# Esp32Relays.net
KiCad netlist of a schematic drawn in EAGLE
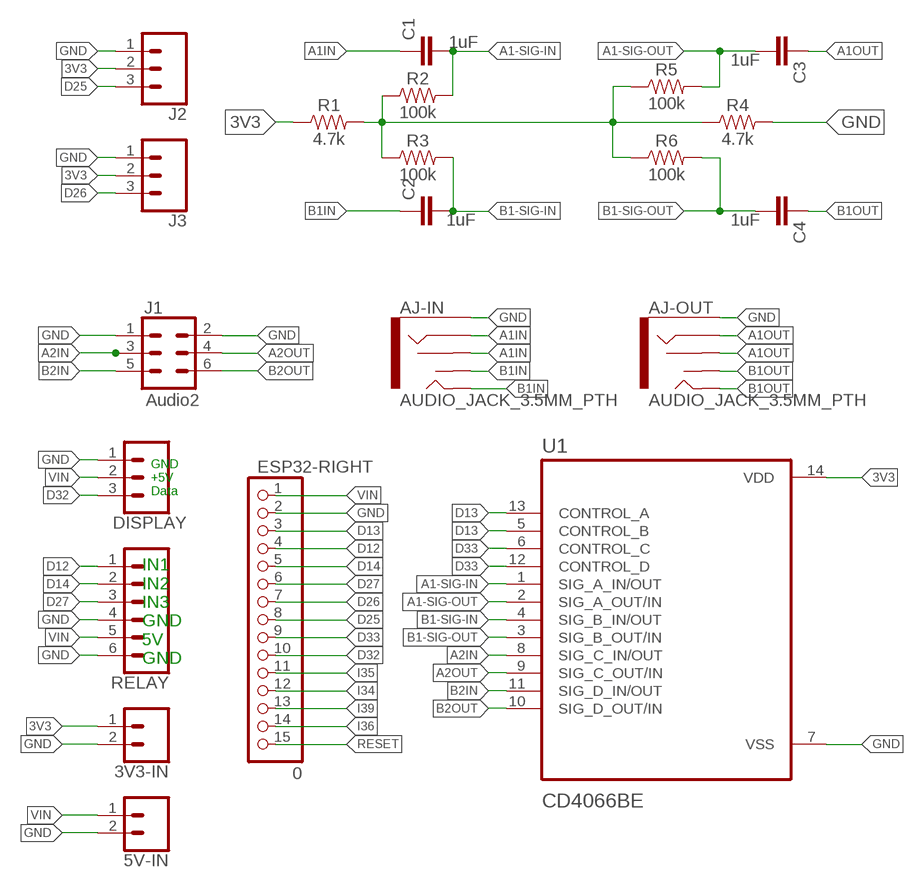
[diagram p0: schematic, sheet 1]

(export (version "E")
  (design (tool "Eeschema 10.0.6"))
  (components
    (comp (ref "3V3-IN")
      (value "CONN_02")
      (footprint "eagle-import:1X02")
      (libsource (lib "eagle-import") (part "CONN_02"))
    )
    (comp (ref "5V-IN")
      (value "CONN_02")
      (footprint "eagle-import:1X02")
      (libsource (lib "eagle-import") (part "CONN_02"))
    )
    (comp (ref "AJ-IN")
      (value "AUDIO_JACK_3.5MM_PTH")
      (footprint "eagle-import:AUDIO-JACK")
      (libsource (lib "eagle-import") (part "AUDIO_JACK_3.5MM_PTH"))
    )
    (comp (ref "AJ-OUT")
      (value "AUDIO_JACK_3.5MM_PTH")
      (footprint "eagle-import:AUDIO-JACK")
      (libsource (lib "eagle-import") (part "AUDIO_JACK_3.5MM_PTH"))
    )
    (comp (ref "C1")
      (value "1uF")
      (footprint "eagle-import:0805")
      (libsource (lib "eagle-import") (part "2.2UF-0805-25V-(+80/-20%)"))
    )
    (comp (ref "C2")
      (value "1uF")
      (footprint "eagle-import:0805")
      (libsource (lib "eagle-import") (part "2.2UF-0805-25V-(+80/-20%)"))
    )
    (comp (ref "C3")
      (value "1uF")
      (footprint "eagle-import:0805")
      (libsource (lib "eagle-import") (part "2.2UF-0805-25V-(+80/-20%)"))
    )
    (comp (ref "C4")
      (value "1uF")
      (footprint "eagle-import:0805")
      (libsource (lib "eagle-import") (part "2.2UF-0805-25V-(+80/-20%)"))
    )
    (comp (ref "DISPLAY")
      (value "CONN_03")
      (footprint "eagle-import:1X03")
      (libsource (lib "eagle-import") (part "CONN_03"))
    )
    (comp (ref "ESP32-RIGHT")
      (value "0")
      (footprint "eagle-import:1X15")
      (libsource (lib "eagle-import") (part "PINHD-1X15"))
    )
    (comp (ref "J1")
      (value "Audio2")
      (footprint "eagle-import:2X3")
      (libsource (lib "eagle-import") (part "CONN_03X2FEMALE"))
    )
    (comp (ref "J2")
      (value "CONN_03")
      (footprint "eagle-import:1X03")
      (libsource (lib "eagle-import") (part "CONN_03"))
    )
    (comp (ref "J3")
      (value "CONN_03")
      (footprint "eagle-import:1X03")
      (libsource (lib "eagle-import") (part "CONN_03"))
    )
    (comp (ref "R1")
      (value "4.7k")
      (footprint "eagle-import:0805")
      (libsource (lib "eagle-import") (part "0.3OHM-0805-1/8W-1%"))
    )
    (comp (ref "R2")
      (value "100k")
      (footprint "eagle-import:0805")
      (libsource (lib "eagle-import") (part "0.3OHM-0805-1/8W-1%"))
    )
    (comp (ref "R3")
      (value "100k")
      (footprint "eagle-import:0805")
      (libsource (lib "eagle-import") (part "0.3OHM-0805-1/8W-1%"))
    )
    (comp (ref "R4")
      (value "4.7k")
      (footprint "eagle-import:0805")
      (libsource (lib "eagle-import") (part "0.3OHM-0805-1/8W-1%"))
    )
    (comp (ref "R5")
      (value "100k")
      (footprint "eagle-import:0805")
      (libsource (lib "eagle-import") (part "0.3OHM-0805-1/8W-1%"))
    )
    (comp (ref "R6")
      (value "100k")
      (footprint "eagle-import:0805")
      (libsource (lib "eagle-import") (part "0.3OHM-0805-1/8W-1%"))
    )
    (comp (ref "RELAY")
      (value "CONN_06NO_SILK_FEMALE_PTH")
      (footprint "eagle-import:1X06_NO_SILK")
      (libsource (lib "eagle-import") (part "CONN_06NO_SILK_FEMALE_PTH"))
    )
    (comp (ref "U1")
      (value "CD4066BE")
      (footprint "eagle-import:DIP794W45P254L1969H508Q14")
      (fields (field (name "MF") "Texas Instruments"))
      (libsource (lib "eagle-import") (part "CD4066BE"))
    )
  )
  (nets
    (net (code "1") (name "3V3") (class "Default")
      (node (ref "3V3-IN") (pin "1") (pinfunction "1_1") (pintype "passive"))
      (node (ref "J2") (pin "2") (pinfunction "2_2") (pintype "passive"))
      (node (ref "J3") (pin "2") (pinfunction "2_2") (pintype "passive"))
      (node (ref "R1") (pin "1") (pinfunction "1_1") (pintype "passive"))
      (node (ref "U1") (pin "14") (pinfunction "VDD_14") (pintype "power_in"))
    )
    (net (code "2") (name "A1-SIG-IN") (class "Default")
      (node (ref "C1") (pin "2") (pinfunction "2_2") (pintype "passive"))
      (node (ref "R2") (pin "2") (pinfunction "2_2") (pintype "passive"))
      (node (ref "U1") (pin "1") (pinfunction "SIG_A_IN/OUT_1") (pintype "input"))
    )
    (net (code "3") (name "A1-SIG-OUT") (class "Default")
      (node (ref "C3") (pin "2") (pinfunction "2_2") (pintype "passive"))
      (node (ref "R5") (pin "2") (pinfunction "2_2") (pintype "passive"))
      (node (ref "U1") (pin "2") (pinfunction "SIG_A_OUT/IN_2") (pintype "input"))
    )
    (net (code "4") (name "A1IN") (class "Default")
      (node (ref "AJ-IN") (pin "RING") (pinfunction "RING_RING") (pintype "bidirectional"))
      (node (ref "AJ-IN") (pin "RSH") (pinfunction "RSH_RSH") (pintype "bidirectional"))
      (node (ref "C1") (pin "1") (pinfunction "1_1") (pintype "passive"))
    )
    (net (code "5") (name "A1OUT") (class "Default")
      (node (ref "AJ-OUT") (pin "RING") (pinfunction "RING_RING") (pintype "bidirectional"))
      (node (ref "AJ-OUT") (pin "RSH") (pinfunction "RSH_RSH") (pintype "bidirectional"))
      (node (ref "C3") (pin "1") (pinfunction "1_1") (pintype "passive"))
    )
    (net (code "6") (name "A2IN") (class "Default")
      (node (ref "J1") (pin "3") (pinfunction "3_3") (pintype "bidirectional"))
      (node (ref "U1") (pin "8") (pinfunction "SIG_C_IN/OUT_8") (pintype "input"))
    )
    (net (code "7") (name "A2OUT") (class "Default")
      (node (ref "J1") (pin "4") (pinfunction "4_4") (pintype "bidirectional"))
      (node (ref "U1") (pin "9") (pinfunction "SIG_C_OUT/IN_9") (pintype "input"))
    )
    (net (code "8") (name "B1-SIG-IN") (class "Default")
      (node (ref "C2") (pin "2") (pinfunction "2_2") (pintype "passive"))
      (node (ref "R3") (pin "2") (pinfunction "2_2") (pintype "passive"))
      (node (ref "U1") (pin "4") (pinfunction "SIG_B_IN/OUT_4") (pintype "input"))
    )
    (net (code "9") (name "B1-SIG-OUT") (class "Default")
      (node (ref "C4") (pin "2") (pinfunction "2_2") (pintype "passive"))
      (node (ref "R6") (pin "2") (pinfunction "2_2") (pintype "passive"))
      (node (ref "U1") (pin "3") (pinfunction "SIG_B_OUT/IN_3") (pintype "input"))
    )
    (net (code "10") (name "B1IN") (class "Default")
      (node (ref "AJ-IN") (pin "TIP") (pinfunction "TIP_TIP") (pintype "bidirectional"))
      (node (ref "AJ-IN") (pin "TSH") (pinfunction "TSH_TSH") (pintype "bidirectional"))
      (node (ref "C2") (pin "1") (pinfunction "1_1") (pintype "passive"))
    )
    (net (code "11") (name "B1OUT") (class "Default")
      (node (ref "AJ-OUT") (pin "TIP") (pinfunction "TIP_TIP") (pintype "bidirectional"))
      (node (ref "AJ-OUT") (pin "TSH") (pinfunction "TSH_TSH") (pintype "bidirectional"))
      (node (ref "C4") (pin "1") (pinfunction "1_1") (pintype "passive"))
    )
    (net (code "12") (name "B2IN") (class "Default")
      (node (ref "J1") (pin "5") (pinfunction "5_5") (pintype "bidirectional"))
      (node (ref "U1") (pin "11") (pinfunction "SIG_D_IN/OUT_11") (pintype "input"))
    )
    (net (code "13") (name "B2OUT") (class "Default")
      (node (ref "J1") (pin "6") (pinfunction "6_6") (pintype "bidirectional"))
      (node (ref "U1") (pin "10") (pinfunction "SIG_D_OUT/IN_10") (pintype "input"))
    )
    (net (code "14") (name "D12") (class "Default")
      (node (ref "ESP32-RIGHT") (pin "4") (pinfunction "4_4") (pintype "passive"))
      (node (ref "RELAY") (pin "1") (pinfunction "1_1") (pintype "passive"))
    )
    (net (code "15") (name "D13") (class "Default")
      (node (ref "ESP32-RIGHT") (pin "3") (pinfunction "3_3") (pintype "passive"))
      (node (ref "U1") (pin "13") (pinfunction "CONTROL_A_13") (pintype "input"))
      (node (ref "U1") (pin "5") (pinfunction "CONTROL_B_5") (pintype "input"))
    )
    (net (code "16") (name "D14") (class "Default")
      (node (ref "ESP32-RIGHT") (pin "5") (pinfunction "5_5") (pintype "passive"))
      (node (ref "RELAY") (pin "2") (pinfunction "2_2") (pintype "passive"))
    )
    (net (code "17") (name "D25") (class "Default")
      (node (ref "ESP32-RIGHT") (pin "8") (pinfunction "8_8") (pintype "passive"))
      (node (ref "J2") (pin "3") (pinfunction "3_3") (pintype "passive"))
    )
    (net (code "18") (name "D26") (class "Default")
      (node (ref "ESP32-RIGHT") (pin "7") (pinfunction "7_7") (pintype "passive"))
      (node (ref "J3") (pin "3") (pinfunction "3_3") (pintype "passive"))
    )
    (net (code "19") (name "D27") (class "Default")
      (node (ref "ESP32-RIGHT") (pin "6") (pinfunction "6_6") (pintype "passive"))
      (node (ref "RELAY") (pin "3") (pinfunction "3_3") (pintype "passive"))
    )
    (net (code "20") (name "D32") (class "Default")
      (node (ref "DISPLAY") (pin "3") (pinfunction "3_3") (pintype "passive"))
      (node (ref "ESP32-RIGHT") (pin "10") (pinfunction "10_10") (pintype "passive"))
    )
    (net (code "21") (name "D33") (class "Default")
      (node (ref "ESP32-RIGHT") (pin "9") (pinfunction "9_9") (pintype "passive"))
      (node (ref "U1") (pin "12") (pinfunction "CONTROL_D_12") (pintype "input"))
      (node (ref "U1") (pin "6") (pinfunction "CONTROL_C_6") (pintype "input"))
    )
    (net (code "22") (name "GND") (class "Default")
      (node (ref "3V3-IN") (pin "2") (pinfunction "2_2") (pintype "passive"))
      (node (ref "5V-IN") (pin "2") (pinfunction "2_2") (pintype "passive"))
      (node (ref "AJ-IN") (pin "SLEEVE") (pinfunction "SLEEVE_SLEEVE") (pintype "bidirectional"))
      (node (ref "AJ-OUT") (pin "SLEEVE") (pinfunction "SLEEVE_SLEEVE") (pintype "bidirectional"))
      (node (ref "DISPLAY") (pin "1") (pinfunction "1_1") (pintype "passive"))
      (node (ref "ESP32-RIGHT") (pin "2") (pinfunction "2_2") (pintype "passive"))
      (node (ref "J1") (pin "1") (pinfunction "1_1") (pintype "bidirectional"))
      (node (ref "J1") (pin "2") (pinfunction "2_2") (pintype "bidirectional"))
      (node (ref "J2") (pin "1") (pinfunction "1_1") (pintype "passive"))
      (node (ref "J3") (pin "1") (pinfunction "1_1") (pintype "passive"))
      (node (ref "R4") (pin "2") (pinfunction "2_2") (pintype "passive"))
      (node (ref "RELAY") (pin "4") (pinfunction "4_4") (pintype "passive"))
      (node (ref "RELAY") (pin "6") (pinfunction "6_6") (pintype "passive"))
      (node (ref "U1") (pin "7") (pinfunction "VSS_7") (pintype "power_in"))
    )
    (net (code "23") (name "I34") (class "Default")
      (node (ref "ESP32-RIGHT") (pin "12") (pinfunction "12_12") (pintype "passive"))
    )
    (net (code "24") (name "I35") (class "Default")
      (node (ref "ESP32-RIGHT") (pin "11") (pinfunction "11_11") (pintype "passive"))
    )
    (net (code "25") (name "I36") (class "Default")
      (node (ref "ESP32-RIGHT") (pin "14") (pinfunction "14_14") (pintype "passive"))
    )
    (net (code "26") (name "I39") (class "Default")
      (node (ref "ESP32-RIGHT") (pin "13") (pinfunction "13_13") (pintype "passive"))
    )
    (net (code "27") (name "Net-(R1-Pad2)") (class "Default")
      (node (ref "R1") (pin "2") (pinfunction "2_2") (pintype "passive"))
      (node (ref "R2") (pin "1") (pinfunction "1_1") (pintype "passive"))
      (node (ref "R3") (pin "1") (pinfunction "1_1") (pintype "passive"))
      (node (ref "R4") (pin "1") (pinfunction "1_1") (pintype "passive"))
      (node (ref "R5") (pin "1") (pinfunction "1_1") (pintype "passive"))
      (node (ref "R6") (pin "1") (pinfunction "1_1") (pintype "passive"))
    )
    (net (code "28") (name "RESET") (class "Default")
      (node (ref "ESP32-RIGHT") (pin "15") (pinfunction "15_15") (pintype "passive"))
    )
    (net (code "29") (name "VIN") (class "Default")
      (node (ref "5V-IN") (pin "1") (pinfunction "1_1") (pintype "passive"))
      (node (ref "DISPLAY") (pin "2") (pinfunction "2_2") (pintype "passive"))
      (node (ref "ESP32-RIGHT") (pin "1") (pinfunction "1_1") (pintype "passive"))
      (node (ref "RELAY") (pin "5") (pinfunction "5_5") (pintype "passive"))
    )
  )
)
